# R201X.net
KiCad netlist of a schematic drawn in EAGLE
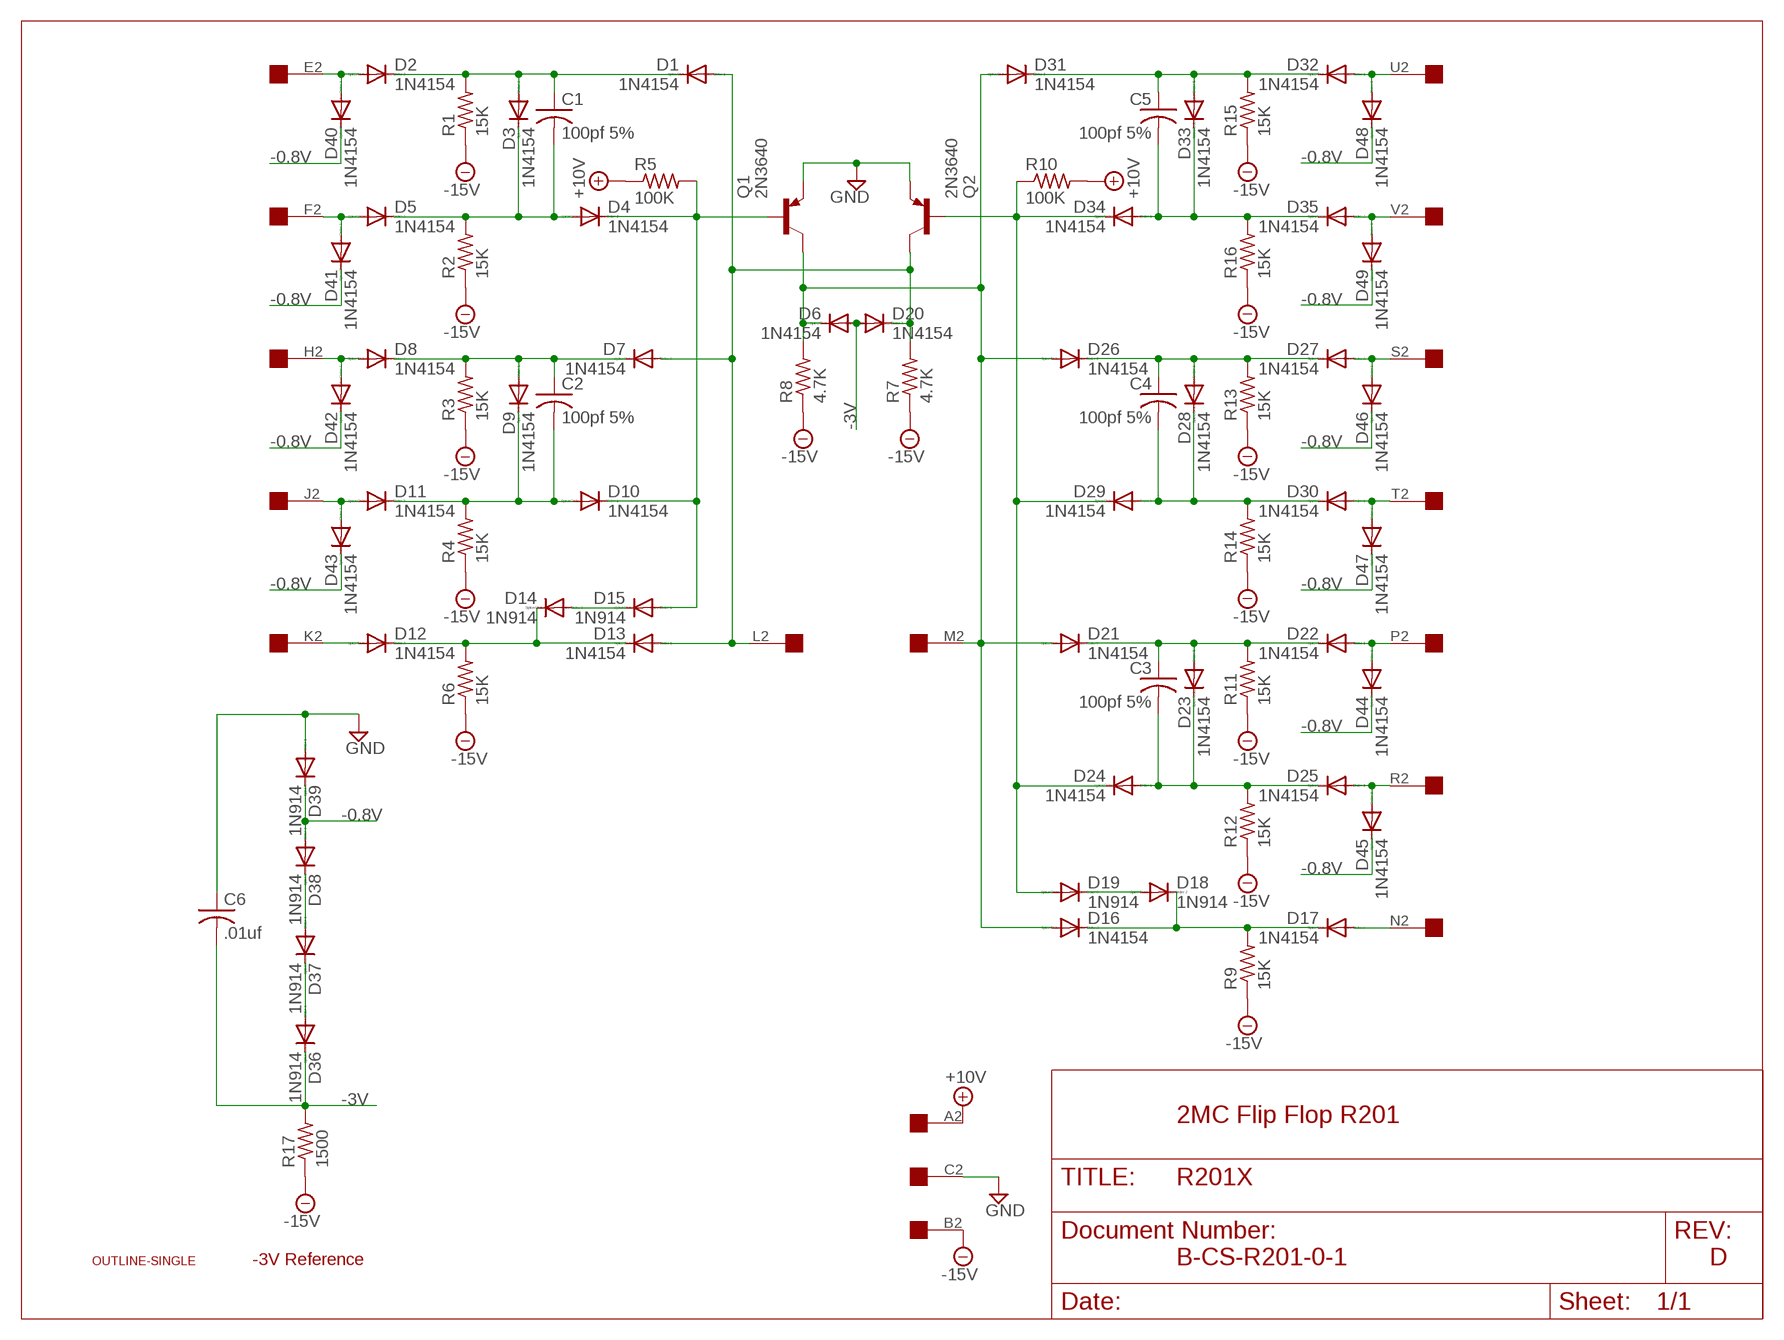
[diagram p0: schematic, sheet 1]

(export (version "E")
  (design (tool "Eeschema 10.0.6"))
  (components
    (comp (ref "C1")
      (value "100pf 5%")
      (footprint "eagle-import:C050-025X075")
      (libsource (lib "eagle-import") (part "C-US050-025X075"))
    )
    (comp (ref "C2")
      (value "100pf 5%")
      (footprint "eagle-import:C050-025X075")
      (libsource (lib "eagle-import") (part "C-US050-025X075"))
    )
    (comp (ref "C3")
      (value "100pf 5%")
      (footprint "eagle-import:C050-025X075")
      (libsource (lib "eagle-import") (part "C-US050-025X075"))
    )
    (comp (ref "C4")
      (value "100pf 5%")
      (footprint "eagle-import:C050-025X075")
      (libsource (lib "eagle-import") (part "C-US050-025X075"))
    )
    (comp (ref "C5")
      (value "100pf 5%")
      (footprint "eagle-import:C050-025X075")
      (libsource (lib "eagle-import") (part "C-US050-025X075"))
    )
    (comp (ref "C6")
      (value ".01uf")
      (footprint "eagle-import:C050-025X075")
      (libsource (lib "eagle-import") (part "C-US050-025X075"))
    )
    (comp (ref "D1")
      (value "1N4154")
      (footprint "eagle-import:DO35-10")
      (libsource (lib "eagle-import") (part "1N4148DO35-10"))
    )
    (comp (ref "D2")
      (value "1N4154")
      (footprint "eagle-import:DO35-10")
      (libsource (lib "eagle-import") (part "1N4148DO35-10"))
    )
    (comp (ref "D3")
      (value "1N4154")
      (footprint "eagle-import:DO35-10")
      (libsource (lib "eagle-import") (part "1N4148DO35-10"))
    )
    (comp (ref "D4")
      (value "1N4154")
      (footprint "eagle-import:DO35-10")
      (libsource (lib "eagle-import") (part "1N4148DO35-10"))
    )
    (comp (ref "D5")
      (value "1N4154")
      (footprint "eagle-import:DO35-10")
      (libsource (lib "eagle-import") (part "1N4148DO35-10"))
    )
    (comp (ref "D6")
      (value "1N4154")
      (footprint "eagle-import:DO35-10")
      (libsource (lib "eagle-import") (part "1N4148DO35-10"))
    )
    (comp (ref "D7")
      (value "1N4154")
      (footprint "eagle-import:DO35-10")
      (libsource (lib "eagle-import") (part "1N4148DO35-10"))
    )
    (comp (ref "D8")
      (value "1N4154")
      (footprint "eagle-import:DO35-10")
      (libsource (lib "eagle-import") (part "1N4148DO35-10"))
    )
    (comp (ref "D9")
      (value "1N4154")
      (footprint "eagle-import:DO35-10")
      (libsource (lib "eagle-import") (part "1N4148DO35-10"))
    )
    (comp (ref "D10")
      (value "1N4154")
      (footprint "eagle-import:DO35-10")
      (libsource (lib "eagle-import") (part "1N4148DO35-10"))
    )
    (comp (ref "D11")
      (value "1N4154")
      (footprint "eagle-import:DO35-10")
      (libsource (lib "eagle-import") (part "1N4148DO35-10"))
    )
    (comp (ref "D12")
      (value "1N4154")
      (footprint "eagle-import:DO35-10")
      (libsource (lib "eagle-import") (part "1N4148DO35-10"))
    )
    (comp (ref "D13")
      (value "1N4154")
      (footprint "eagle-import:DO35-10")
      (libsource (lib "eagle-import") (part "1N4148DO35-10"))
    )
    (comp (ref "D14")
      (value "1N914")
      (footprint "eagle-import:DO35-10")
      (libsource (lib "eagle-import") (part "1N4148DO35-10"))
    )
    (comp (ref "D15")
      (value "1N914")
      (footprint "eagle-import:DO35-10")
      (libsource (lib "eagle-import") (part "1N4148DO35-10"))
    )
    (comp (ref "D16")
      (value "1N4154")
      (footprint "eagle-import:DO35-10")
      (libsource (lib "eagle-import") (part "1N4148DO35-10"))
    )
    (comp (ref "D17")
      (value "1N4154")
      (footprint "eagle-import:DO35-10")
      (libsource (lib "eagle-import") (part "1N4148DO35-10"))
    )
    (comp (ref "D18")
      (value "1N914")
      (footprint "eagle-import:DO35-10")
      (libsource (lib "eagle-import") (part "1N4148DO35-10"))
    )
    (comp (ref "D19")
      (value "1N914")
      (footprint "eagle-import:DO35-10")
      (libsource (lib "eagle-import") (part "1N4148DO35-10"))
    )
    (comp (ref "D20")
      (value "1N4154")
      (footprint "eagle-import:DO35-10")
      (libsource (lib "eagle-import") (part "1N4148DO35-10"))
    )
    (comp (ref "D21")
      (value "1N4154")
      (footprint "eagle-import:DO35-10")
      (libsource (lib "eagle-import") (part "1N4148DO35-10"))
    )
    (comp (ref "D22")
      (value "1N4154")
      (footprint "eagle-import:DO35-10")
      (libsource (lib "eagle-import") (part "1N4148DO35-10"))
    )
    (comp (ref "D23")
      (value "1N4154")
      (footprint "eagle-import:DO35-10")
      (libsource (lib "eagle-import") (part "1N4148DO35-10"))
    )
    (comp (ref "D24")
      (value "1N4154")
      (footprint "eagle-import:DO35-10")
      (libsource (lib "eagle-import") (part "1N4148DO35-10"))
    )
    (comp (ref "D25")
      (value "1N4154")
      (footprint "eagle-import:DO35-10")
      (libsource (lib "eagle-import") (part "1N4148DO35-10"))
    )
    (comp (ref "D26")
      (value "1N4154")
      (footprint "eagle-import:DO35-10")
      (libsource (lib "eagle-import") (part "1N4148DO35-10"))
    )
    (comp (ref "D27")
      (value "1N4154")
      (footprint "eagle-import:DO35-10")
      (libsource (lib "eagle-import") (part "1N4148DO35-10"))
    )
    (comp (ref "D28")
      (value "1N4154")
      (footprint "eagle-import:DO35-10")
      (libsource (lib "eagle-import") (part "1N4148DO35-10"))
    )
    (comp (ref "D29")
      (value "1N4154")
      (footprint "eagle-import:DO35-10")
      (libsource (lib "eagle-import") (part "1N4148DO35-10"))
    )
    (comp (ref "D30")
      (value "1N4154")
      (footprint "eagle-import:DO35-10")
      (libsource (lib "eagle-import") (part "1N4148DO35-10"))
    )
    (comp (ref "D31")
      (value "1N4154")
      (footprint "eagle-import:DO35-10")
      (libsource (lib "eagle-import") (part "1N4148DO35-10"))
    )
    (comp (ref "D32")
      (value "1N4154")
      (footprint "eagle-import:DO35-10")
      (libsource (lib "eagle-import") (part "1N4148DO35-10"))
    )
    (comp (ref "D33")
      (value "1N4154")
      (footprint "eagle-import:DO35-10")
      (libsource (lib "eagle-import") (part "1N4148DO35-10"))
    )
    (comp (ref "D34")
      (value "1N4154")
      (footprint "eagle-import:DO35-10")
      (libsource (lib "eagle-import") (part "1N4148DO35-10"))
    )
    (comp (ref "D35")
      (value "1N4154")
      (footprint "eagle-import:DO35-10")
      (libsource (lib "eagle-import") (part "1N4148DO35-10"))
    )
    (comp (ref "D36")
      (value "1N914")
      (footprint "eagle-import:DO35-10")
      (libsource (lib "eagle-import") (part "1N4148DO35-10"))
    )
    (comp (ref "D37")
      (value "1N914")
      (footprint "eagle-import:DO35-10")
      (libsource (lib "eagle-import") (part "1N4148DO35-10"))
    )
    (comp (ref "D38")
      (value "1N914")
      (footprint "eagle-import:DO35-10")
      (libsource (lib "eagle-import") (part "1N4148DO35-10"))
    )
    (comp (ref "D39")
      (value "1N914")
      (footprint "eagle-import:DO35-10")
      (libsource (lib "eagle-import") (part "1N4148DO35-10"))
    )
    (comp (ref "D40")
      (value "1N4154")
      (footprint "eagle-import:DO35-10")
      (libsource (lib "eagle-import") (part "1N4148DO35-10"))
    )
    (comp (ref "D41")
      (value "1N4154")
      (footprint "eagle-import:DO35-10")
      (libsource (lib "eagle-import") (part "1N4148DO35-10"))
    )
    (comp (ref "D42")
      (value "1N4154")
      (footprint "eagle-import:DO35-10")
      (libsource (lib "eagle-import") (part "1N4148DO35-10"))
    )
    (comp (ref "D43")
      (value "1N4154")
      (footprint "eagle-import:DO35-10")
      (libsource (lib "eagle-import") (part "1N4148DO35-10"))
    )
    (comp (ref "D44")
      (value "1N4154")
      (footprint "eagle-import:DO35-10")
      (libsource (lib "eagle-import") (part "1N4148DO35-10"))
    )
    (comp (ref "D45")
      (value "1N4154")
      (footprint "eagle-import:DO35-10")
      (libsource (lib "eagle-import") (part "1N4148DO35-10"))
    )
    (comp (ref "D46")
      (value "1N4154")
      (footprint "eagle-import:DO35-10")
      (libsource (lib "eagle-import") (part "1N4148DO35-10"))
    )
    (comp (ref "D47")
      (value "1N4154")
      (footprint "eagle-import:DO35-10")
      (libsource (lib "eagle-import") (part "1N4148DO35-10"))
    )
    (comp (ref "D48")
      (value "1N4154")
      (footprint "eagle-import:DO35-10")
      (libsource (lib "eagle-import") (part "1N4148DO35-10"))
    )
    (comp (ref "D49")
      (value "1N4154")
      (footprint "eagle-import:DO35-10")
      (libsource (lib "eagle-import") (part "1N4148DO35-10"))
    )
    (comp (ref "Q1")
      (value "2N3640")
      (footprint "eagle-import:TO39")
      (libsource (lib "eagle-import") (part "2N3637"))
    )
    (comp (ref "Q2")
      (value "2N3640")
      (footprint "eagle-import:TO39")
      (libsource (lib "eagle-import") (part "2N3637"))
    )
    (comp (ref "R1")
      (value "15K")
      (footprint "eagle-import:0207_10")
      (libsource (lib "eagle-import") (part "R-US_0207/10"))
    )
    (comp (ref "R2")
      (value "15K")
      (footprint "eagle-import:0207_10")
      (libsource (lib "eagle-import") (part "R-US_0207/10"))
    )
    (comp (ref "R3")
      (value "15K")
      (footprint "eagle-import:0207_10")
      (libsource (lib "eagle-import") (part "R-US_0207/10"))
    )
    (comp (ref "R4")
      (value "15K")
      (footprint "eagle-import:0207_10")
      (libsource (lib "eagle-import") (part "R-US_0207/10"))
    )
    (comp (ref "R5")
      (value "100K")
      (footprint "eagle-import:0207_10")
      (libsource (lib "eagle-import") (part "R-US_0207/10"))
    )
    (comp (ref "R6")
      (value "15K")
      (footprint "eagle-import:0207_10")
      (libsource (lib "eagle-import") (part "R-US_0207/10"))
    )
    (comp (ref "R7")
      (value "4.7K")
      (footprint "eagle-import:0207_10")
      (libsource (lib "eagle-import") (part "R-US_0207/10"))
    )
    (comp (ref "R8")
      (value "4.7K")
      (footprint "eagle-import:0207_10")
      (libsource (lib "eagle-import") (part "R-US_0207/10"))
    )
    (comp (ref "R9")
      (value "15K")
      (footprint "eagle-import:0207_10")
      (libsource (lib "eagle-import") (part "R-US_0207/10"))
    )
    (comp (ref "R10")
      (value "100K")
      (footprint "eagle-import:0207_10")
      (libsource (lib "eagle-import") (part "R-US_0207/10"))
    )
    (comp (ref "R11")
      (value "15K")
      (footprint "eagle-import:0207_10")
      (libsource (lib "eagle-import") (part "R-US_0207/10"))
    )
    (comp (ref "R12")
      (value "15K")
      (footprint "eagle-import:0207_10")
      (libsource (lib "eagle-import") (part "R-US_0207/10"))
    )
    (comp (ref "R13")
      (value "15K")
      (footprint "eagle-import:0207_10")
      (libsource (lib "eagle-import") (part "R-US_0207/10"))
    )
    (comp (ref "R14")
      (value "15K")
      (footprint "eagle-import:0207_10")
      (libsource (lib "eagle-import") (part "R-US_0207/10"))
    )
    (comp (ref "R15")
      (value "15K")
      (footprint "eagle-import:0207_10")
      (libsource (lib "eagle-import") (part "R-US_0207/10"))
    )
    (comp (ref "R16")
      (value "15K")
      (footprint "eagle-import:0207_10")
      (libsource (lib "eagle-import") (part "R-US_0207/10"))
    )
    (comp (ref "R17")
      (value "1500")
      (footprint "eagle-import:0207_10")
      (libsource (lib "eagle-import") (part "R-US_0207/10"))
    )
    (comp (ref "U$1")
      (value "OUTLINE-SINGLE")
      (footprint "eagle-import:SINGLE")
      (libsource (lib "eagle-import") (part "OUTLINE-SINGLE"))
    )
    (comp (ref "U$2")
      (value "EDGE-1")
      (footprint "eagle-import:EDGE-CON1")
      (libsource (lib "eagle-import") (part "EDGE-1"))
    )
  )
  (nets
    (net (code "1") (name "+10V") (class "Default")
      (node (ref "R10") (pin "2") (pinfunction "2_2") (pintype "passive"))
      (node (ref "R5") (pin "1") (pinfunction "1_1") (pintype "passive"))
      (node (ref "U$2") (pin "A2") (pinfunction "1_A2") (pintype "bidirectional"))
    )
    (net (code "2") (name "-15V") (class "Default")
      (node (ref "R1") (pin "1") (pinfunction "1_1") (pintype "passive"))
      (node (ref "R11") (pin "1") (pinfunction "1_1") (pintype "passive"))
      (node (ref "R12") (pin "1") (pinfunction "1_1") (pintype "passive"))
      (node (ref "R13") (pin "1") (pinfunction "1_1") (pintype "passive"))
      (node (ref "R14") (pin "1") (pinfunction "1_1") (pintype "passive"))
      (node (ref "R15") (pin "1") (pinfunction "1_1") (pintype "passive"))
      (node (ref "R16") (pin "1") (pinfunction "1_1") (pintype "passive"))
      (node (ref "R17") (pin "1") (pinfunction "1_1") (pintype "passive"))
      (node (ref "R2") (pin "1") (pinfunction "1_1") (pintype "passive"))
      (node (ref "R3") (pin "1") (pinfunction "1_1") (pintype "passive"))
      (node (ref "R4") (pin "1") (pinfunction "1_1") (pintype "passive"))
      (node (ref "R6") (pin "1") (pinfunction "1_1") (pintype "passive"))
      (node (ref "R7") (pin "1") (pinfunction "1_1") (pintype "passive"))
      (node (ref "R8") (pin "1") (pinfunction "1_1") (pintype "passive"))
      (node (ref "R9") (pin "1") (pinfunction "1_1") (pintype "passive"))
      (node (ref "U$2") (pin "B2") (pinfunction "1_B2") (pintype "bidirectional"))
    )
    (net (code "3") (name "/-0.8V") (class "Default")
      (node (ref "D38") (pin "A") (pinfunction "A_A") (pintype "passive"))
      (node (ref "D39") (pin "C") (pinfunction "C_C") (pintype "passive"))
      (node (ref "D40") (pin "C") (pinfunction "C_C") (pintype "passive"))
      (node (ref "D41") (pin "C") (pinfunction "C_C") (pintype "passive"))
      (node (ref "D42") (pin "C") (pinfunction "C_C") (pintype "passive"))
      (node (ref "D43") (pin "C") (pinfunction "C_C") (pintype "passive"))
      (node (ref "D44") (pin "C") (pinfunction "C_C") (pintype "passive"))
      (node (ref "D45") (pin "C") (pinfunction "C_C") (pintype "passive"))
      (node (ref "D46") (pin "C") (pinfunction "C_C") (pintype "passive"))
      (node (ref "D47") (pin "C") (pinfunction "C_C") (pintype "passive"))
      (node (ref "D48") (pin "C") (pinfunction "C_C") (pintype "passive"))
      (node (ref "D49") (pin "C") (pinfunction "C_C") (pintype "passive"))
    )
    (net (code "4") (name "/-3V") (class "Default")
      (node (ref "C6") (pin "2") (pinfunction "2_2") (pintype "passive"))
      (node (ref "D20") (pin "A") (pinfunction "A_A") (pintype "passive"))
      (node (ref "D36") (pin "C") (pinfunction "C_C") (pintype "passive"))
      (node (ref "D6") (pin "A") (pinfunction "A_A") (pintype "passive"))
      (node (ref "R17") (pin "2") (pinfunction "2_2") (pintype "passive"))
    )
    (net (code "5") (name "GND") (class "Default")
      (node (ref "C6") (pin "1") (pinfunction "1_1") (pintype "passive"))
      (node (ref "D39") (pin "A") (pinfunction "A_A") (pintype "passive"))
      (node (ref "Q1") (pin "1") (pinfunction "E_1") (pintype "passive"))
      (node (ref "Q2") (pin "1") (pinfunction "E_1") (pintype "passive"))
      (node (ref "U$2") (pin "C2") (pinfunction "1_C2") (pintype "bidirectional"))
    )
    (net (code "6") (name "Net-(C1-Pad1)") (class "Default")
      (node (ref "C1") (pin "1") (pinfunction "1_1") (pintype "passive"))
      (node (ref "D1") (pin "C") (pinfunction "C_C") (pintype "passive"))
      (node (ref "D2") (pin "C") (pinfunction "C_C") (pintype "passive"))
      (node (ref "D3") (pin "A") (pinfunction "A_A") (pintype "passive"))
      (node (ref "R1") (pin "2") (pinfunction "2_2") (pintype "passive"))
    )
    (net (code "7") (name "Net-(C1-Pad2)") (class "Default")
      (node (ref "C1") (pin "2") (pinfunction "2_2") (pintype "passive"))
      (node (ref "D3") (pin "C") (pinfunction "C_C") (pintype "passive"))
      (node (ref "D4") (pin "A") (pinfunction "A_A") (pintype "passive"))
      (node (ref "D5") (pin "C") (pinfunction "C_C") (pintype "passive"))
      (node (ref "R2") (pin "2") (pinfunction "2_2") (pintype "passive"))
    )
    (net (code "8") (name "Net-(C2-Pad1)") (class "Default")
      (node (ref "C2") (pin "1") (pinfunction "1_1") (pintype "passive"))
      (node (ref "D7") (pin "C") (pinfunction "C_C") (pintype "passive"))
      (node (ref "D8") (pin "C") (pinfunction "C_C") (pintype "passive"))
      (node (ref "D9") (pin "A") (pinfunction "A_A") (pintype "passive"))
      (node (ref "R3") (pin "2") (pinfunction "2_2") (pintype "passive"))
    )
    (net (code "9") (name "Net-(C2-Pad2)") (class "Default")
      (node (ref "C2") (pin "2") (pinfunction "2_2") (pintype "passive"))
      (node (ref "D10") (pin "A") (pinfunction "A_A") (pintype "passive"))
      (node (ref "D11") (pin "C") (pinfunction "C_C") (pintype "passive"))
      (node (ref "D9") (pin "C") (pinfunction "C_C") (pintype "passive"))
      (node (ref "R4") (pin "2") (pinfunction "2_2") (pintype "passive"))
    )
    (net (code "10") (name "Net-(C3-Pad1)") (class "Default")
      (node (ref "C3") (pin "1") (pinfunction "1_1") (pintype "passive"))
      (node (ref "D21") (pin "C") (pinfunction "C_C") (pintype "passive"))
      (node (ref "D22") (pin "C") (pinfunction "C_C") (pintype "passive"))
      (node (ref "D23") (pin "A") (pinfunction "A_A") (pintype "passive"))
      (node (ref "R11") (pin "2") (pinfunction "2_2") (pintype "passive"))
    )
    (net (code "11") (name "Net-(C3-Pad2)") (class "Default")
      (node (ref "C3") (pin "2") (pinfunction "2_2") (pintype "passive"))
      (node (ref "D23") (pin "C") (pinfunction "C_C") (pintype "passive"))
      (node (ref "D24") (pin "A") (pinfunction "A_A") (pintype "passive"))
      (node (ref "D25") (pin "C") (pinfunction "C_C") (pintype "passive"))
      (node (ref "R12") (pin "2") (pinfunction "2_2") (pintype "passive"))
    )
    (net (code "12") (name "Net-(C4-Pad1)") (class "Default")
      (node (ref "C4") (pin "1") (pinfunction "1_1") (pintype "passive"))
      (node (ref "D26") (pin "C") (pinfunction "C_C") (pintype "passive"))
      (node (ref "D27") (pin "C") (pinfunction "C_C") (pintype "passive"))
      (node (ref "D28") (pin "A") (pinfunction "A_A") (pintype "passive"))
      (node (ref "R13") (pin "2") (pinfunction "2_2") (pintype "passive"))
    )
    (net (code "13") (name "Net-(C4-Pad2)") (class "Default")
      (node (ref "C4") (pin "2") (pinfunction "2_2") (pintype "passive"))
      (node (ref "D28") (pin "C") (pinfunction "C_C") (pintype "passive"))
      (node (ref "D29") (pin "A") (pinfunction "A_A") (pintype "passive"))
      (node (ref "D30") (pin "C") (pinfunction "C_C") (pintype "passive"))
      (node (ref "R14") (pin "2") (pinfunction "2_2") (pintype "passive"))
    )
    (net (code "14") (name "Net-(C5-Pad1)") (class "Default")
      (node (ref "C5") (pin "1") (pinfunction "1_1") (pintype "passive"))
      (node (ref "D31") (pin "C") (pinfunction "C_C") (pintype "passive"))
      (node (ref "D32") (pin "C") (pinfunction "C_C") (pintype "passive"))
      (node (ref "D33") (pin "A") (pinfunction "A_A") (pintype "passive"))
      (node (ref "R15") (pin "2") (pinfunction "2_2") (pintype "passive"))
    )
    (net (code "15") (name "Net-(C5-Pad2)") (class "Default")
      (node (ref "C5") (pin "2") (pinfunction "2_2") (pintype "passive"))
      (node (ref "D33") (pin "C") (pinfunction "C_C") (pintype "passive"))
      (node (ref "D34") (pin "A") (pinfunction "A_A") (pintype "passive"))
      (node (ref "D35") (pin "C") (pinfunction "C_C") (pintype "passive"))
      (node (ref "R16") (pin "2") (pinfunction "2_2") (pintype "passive"))
    )
    (net (code "16") (name "Net-(D12-PadC)") (class "Default")
      (node (ref "D12") (pin "C") (pinfunction "C_C") (pintype "passive"))
      (node (ref "D13") (pin "C") (pinfunction "C_C") (pintype "passive"))
      (node (ref "D14") (pin "C") (pinfunction "C_C") (pintype "passive"))
      (node (ref "R6") (pin "2") (pinfunction "2_2") (pintype "passive"))
    )
    (net (code "17") (name "Net-(D14-PadA)") (class "Default")
      (node (ref "D14") (pin "A") (pinfunction "A_A") (pintype "passive"))
      (node (ref "D15") (pin "C") (pinfunction "C_C") (pintype "passive"))
    )
    (net (code "18") (name "Net-(D16-PadC)") (class "Default")
      (node (ref "D16") (pin "C") (pinfunction "C_C") (pintype "passive"))
      (node (ref "D17") (pin "C") (pinfunction "C_C") (pintype "passive"))
      (node (ref "D18") (pin "C") (pinfunction "C_C") (pintype "passive"))
      (node (ref "R9") (pin "2") (pinfunction "2_2") (pintype "passive"))
    )
    (net (code "19") (name "Net-(D18-PadA)") (class "Default")
      (node (ref "D18") (pin "A") (pinfunction "A_A") (pintype "passive"))
      (node (ref "D19") (pin "C") (pinfunction "C_C") (pintype "passive"))
    )
    (net (code "20") (name "Net-(D36-PadA)") (class "Default")
      (node (ref "D36") (pin "A") (pinfunction "A_A") (pintype "passive"))
      (node (ref "D37") (pin "C") (pinfunction "C_C") (pintype "passive"))
    )
    (net (code "21") (name "Net-(D37-PadA)") (class "Default")
      (node (ref "D37") (pin "A") (pinfunction "A_A") (pintype "passive"))
      (node (ref "D38") (pin "C") (pinfunction "C_C") (pintype "passive"))
    )
    (net (code "22") (name "Net-(Q1-B)") (class "Default")
      (node (ref "D10") (pin "C") (pinfunction "C_C") (pintype "passive"))
      (node (ref "D15") (pin "A") (pinfunction "A_A") (pintype "passive"))
      (node (ref "D4") (pin "C") (pinfunction "C_C") (pintype "passive"))
      (node (ref "Q1") (pin "2") (pinfunction "B_2") (pintype "passive"))
      (node (ref "R5") (pin "2") (pinfunction "2_2") (pintype "passive"))
    )
    (net (code "23") (name "Net-(Q1-C)") (class "Default")
      (node (ref "D16") (pin "A") (pinfunction "A_A") (pintype "passive"))
      (node (ref "D21") (pin "A") (pinfunction "A_A") (pintype "passive"))
      (node (ref "D26") (pin "A") (pinfunction "A_A") (pintype "passive"))
      (node (ref "D31") (pin "A") (pinfunction "A_A") (pintype "passive"))
      (node (ref "D6") (pin "C") (pinfunction "C_C") (pintype "passive"))
      (node (ref "Q1") (pin "3") (pinfunction "C_3") (pintype "passive"))
      (node (ref "R8") (pin "2") (pinfunction "2_2") (pintype "passive"))
      (node (ref "U$2") (pin "M2") (pinfunction "1_M2") (pintype "bidirectional"))
    )
    (net (code "24") (name "Net-(Q2-B)") (class "Default")
      (node (ref "D19") (pin "A") (pinfunction "A_A") (pintype "passive"))
      (node (ref "D24") (pin "C") (pinfunction "C_C") (pintype "passive"))
      (node (ref "D29") (pin "C") (pinfunction "C_C") (pintype "passive"))
      (node (ref "D34") (pin "C") (pinfunction "C_C") (pintype "passive"))
      (node (ref "Q2") (pin "2") (pinfunction "B_2") (pintype "passive"))
      (node (ref "R10") (pin "1") (pinfunction "1_1") (pintype "passive"))
    )
    (net (code "25") (name "Net-(Q2-C)") (class "Default")
      (node (ref "D1") (pin "A") (pinfunction "A_A") (pintype "passive"))
      (node (ref "D13") (pin "A") (pinfunction "A_A") (pintype "passive"))
      (node (ref "D20") (pin "C") (pinfunction "C_C") (pintype "passive"))
      (node (ref "D7") (pin "A") (pinfunction "A_A") (pintype "passive"))
      (node (ref "Q2") (pin "3") (pinfunction "C_3") (pintype "passive"))
      (node (ref "R7") (pin "2") (pinfunction "2_2") (pintype "passive"))
      (node (ref "U$2") (pin "L2") (pinfunction "1_L2") (pintype "bidirectional"))
    )
    (net (code "26") (name "Net-(U$2E-1)") (class "Default")
      (node (ref "D2") (pin "A") (pinfunction "A_A") (pintype "passive"))
      (node (ref "D40") (pin "A") (pinfunction "A_A") (pintype "passive"))
      (node (ref "U$2") (pin "E2") (pinfunction "1_E2") (pintype "bidirectional"))
    )
    (net (code "27") (name "Net-(U$2F-1)") (class "Default")
      (node (ref "D41") (pin "A") (pinfunction "A_A") (pintype "passive"))
      (node (ref "D5") (pin "A") (pinfunction "A_A") (pintype "passive"))
      (node (ref "U$2") (pin "F2") (pinfunction "1_F2") (pintype "bidirectional"))
    )
    (net (code "28") (name "Net-(U$2G-1)") (class "Default")
      (node (ref "D42") (pin "A") (pinfunction "A_A") (pintype "passive"))
      (node (ref "D8") (pin "A") (pinfunction "A_A") (pintype "passive"))
      (node (ref "U$2") (pin "H2") (pinfunction "1_H2") (pintype "bidirectional"))
    )
    (net (code "29") (name "Net-(U$2H-1)") (class "Default")
      (node (ref "D11") (pin "A") (pinfunction "A_A") (pintype "passive"))
      (node (ref "D43") (pin "A") (pinfunction "A_A") (pintype "passive"))
      (node (ref "U$2") (pin "J2") (pinfunction "1_J2") (pintype "bidirectional"))
    )
    (net (code "30") (name "Net-(U$2I-1)") (class "Default")
      (node (ref "D12") (pin "A") (pinfunction "A_A") (pintype "passive"))
      (node (ref "U$2") (pin "K2") (pinfunction "1_K2") (pintype "bidirectional"))
    )
    (net (code "31") (name "Net-(U$2L-1)") (class "Default")
      (node (ref "D17") (pin "A") (pinfunction "A_A") (pintype "passive"))
      (node (ref "U$2") (pin "N2") (pinfunction "1_N2") (pintype "bidirectional"))
    )
    (net (code "32") (name "Net-(U$2M-1)") (class "Default")
      (node (ref "D22") (pin "A") (pinfunction "A_A") (pintype "passive"))
      (node (ref "D44") (pin "A") (pinfunction "A_A") (pintype "passive"))
      (node (ref "U$2") (pin "P2") (pinfunction "1_P2") (pintype "bidirectional"))
    )
    (net (code "33") (name "Net-(U$2N-1)") (class "Default")
      (node (ref "D25") (pin "A") (pinfunction "A_A") (pintype "passive"))
      (node (ref "D45") (pin "A") (pinfunction "A_A") (pintype "passive"))
      (node (ref "U$2") (pin "R2") (pinfunction "1_R2") (pintype "bidirectional"))
    )
    (net (code "34") (name "Net-(U$2O-1)") (class "Default")
      (node (ref "D27") (pin "A") (pinfunction "A_A") (pintype "passive"))
      (node (ref "D46") (pin "A") (pinfunction "A_A") (pintype "passive"))
      (node (ref "U$2") (pin "S2") (pinfunction "1_S2") (pintype "bidirectional"))
    )
    (net (code "35") (name "Net-(U$2P-1)") (class "Default")
      (node (ref "D30") (pin "A") (pinfunction "A_A") (pintype "passive"))
      (node (ref "D47") (pin "A") (pinfunction "A_A") (pintype "passive"))
      (node (ref "U$2") (pin "T2") (pinfunction "1_T2") (pintype "bidirectional"))
    )
    (net (code "36") (name "Net-(U$2Q-1)") (class "Default")
      (node (ref "D32") (pin "A") (pinfunction "A_A") (pintype "passive"))
      (node (ref "D48") (pin "A") (pinfunction "A_A") (pintype "passive"))
      (node (ref "U$2") (pin "U2") (pinfunction "1_U2") (pintype "bidirectional"))
    )
    (net (code "37") (name "Net-(U$2R-1)") (class "Default")
      (node (ref "D35") (pin "A") (pinfunction "A_A") (pintype "passive"))
      (node (ref "D49") (pin "A") (pinfunction "A_A") (pintype "passive"))
      (node (ref "U$2") (pin "V2") (pinfunction "1_V2") (pintype "bidirectional"))
    )
  )
)
